# Controller_main.net
KiCad netlist of a schematic drawn in EAGLE
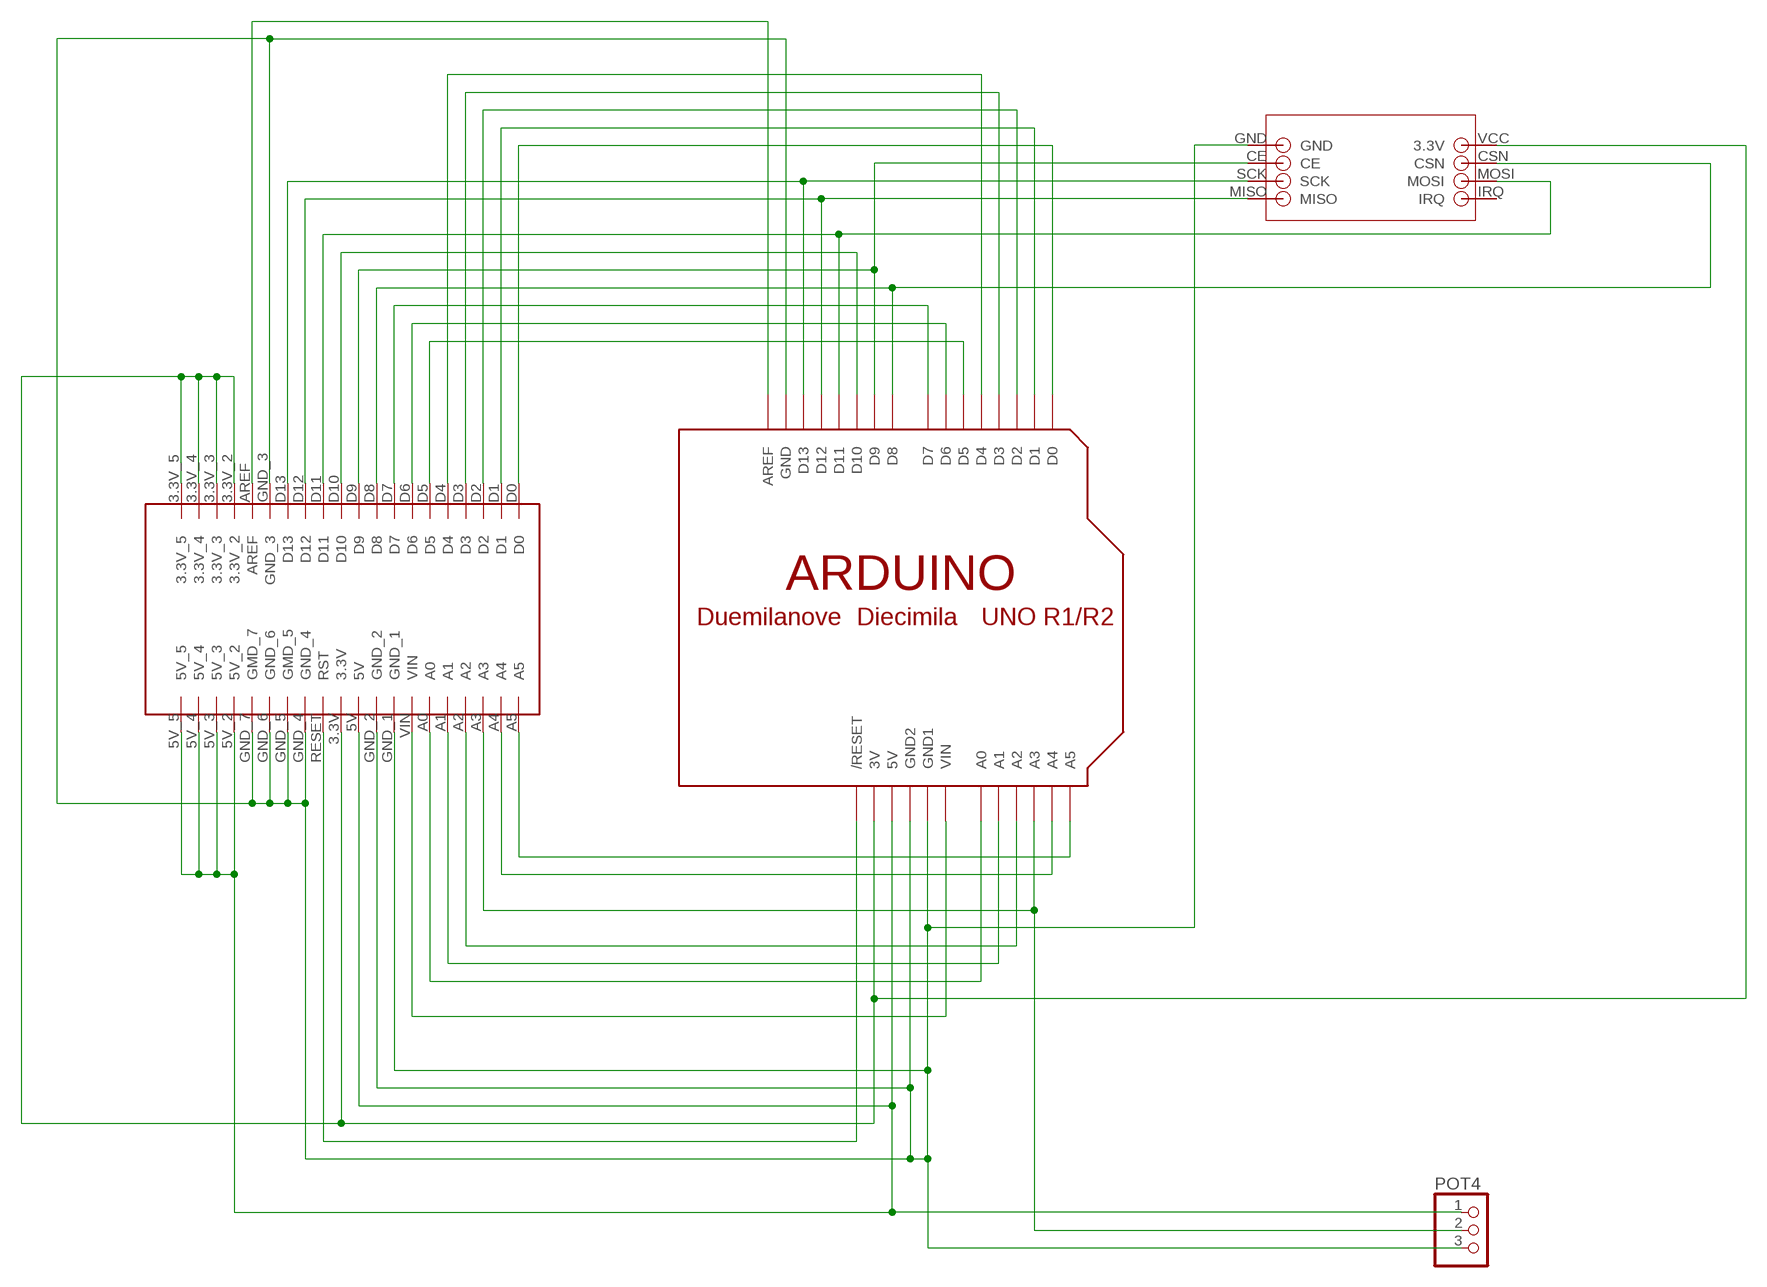
[diagram p0: schematic, sheet 1]

(export (version "E")
  (design (tool "Eeschema 10.0.6"))
  (components
    (comp (ref "2X40CONECTOR1")
      (value "2X40_CONNECTOR")
      (footprint "eagle-import:2X40_PIN_CONNECTOR")
      (libsource (lib "eagle-import") (part "2X40_CONNECTOR"))
    )
    (comp (ref "NRF24L1")
      (value "NRF24L01")
      (footprint "eagle-import:NRF24L01")
      (libsource (lib "eagle-import") (part "NRF24L01"))
    )
    (comp (ref "POT4")
      (value "PINHD-1X3")
      (footprint "eagle-import:1X03")
      (libsource (lib "eagle-import") (part "PINHD-1X3"))
    )
    (comp (ref "U$1")
      (value "ARDUINOUNO")
      (footprint "eagle-import:ARDUINO")
      (libsource (lib "eagle-import") (part "ARDUINOUNO"))
    )
  )
  (nets
    (net (code "1") (name "Net-(2X40CONECTOR1-GMD_5)") (class "Default")
      (node (ref "2X40CONECTOR1") (pin "GND_1") (pinfunction "GND_1_GND_1") (pintype "bidirectional"))
      (node (ref "2X40CONECTOR1") (pin "GND_2") (pinfunction "GND_2_GND_2") (pintype "bidirectional"))
      (node (ref "2X40CONECTOR1") (pin "GND_3") (pinfunction "GND_3_GND_3") (pintype "bidirectional"))
      (node (ref "2X40CONECTOR1") (pin "GND_4") (pinfunction "GND_4_GND_4") (pintype "bidirectional"))
      (node (ref "2X40CONECTOR1") (pin "GND_5") (pinfunction "GMD_5_GND_5") (pintype "bidirectional"))
      (node (ref "2X40CONECTOR1") (pin "GND_6") (pinfunction "GND_6_GND_6") (pintype "bidirectional"))
      (node (ref "2X40CONECTOR1") (pin "GND_7") (pinfunction "GMD_7_GND_7") (pintype "bidirectional"))
      (node (ref "NRF24L1") (pin "GND") (pinfunction "GND_GND") (pintype "bidirectional"))
      (node (ref "POT4") (pin "3") (pinfunction "3_3") (pintype "passive"))
      (node (ref "U$1") (pin "GND") (pinfunction "GND_GND") (pintype "power_in"))
      (node (ref "U$1") (pin "GND1") (pinfunction "GND1_GND1") (pintype "power_in"))
      (node (ref "U$1") (pin "GND2") (pinfunction "GND2_GND2") (pintype "power_in"))
    )
    (net (code "2") (name "Net-(2X40CONECTOR1-Pad5V)") (class "Default")
      (node (ref "2X40CONECTOR1") (pin "5V") (pinfunction "5V_5V") (pintype "bidirectional"))
      (node (ref "2X40CONECTOR1") (pin "5V_2") (pinfunction "5V_2_5V_2") (pintype "bidirectional"))
      (node (ref "2X40CONECTOR1") (pin "5V_3") (pinfunction "5V_3_5V_3") (pintype "bidirectional"))
      (node (ref "2X40CONECTOR1") (pin "5V_4") (pinfunction "5V_4_5V_4") (pintype "bidirectional"))
      (node (ref "2X40CONECTOR1") (pin "5V_5") (pinfunction "5V_5_5V_5") (pintype "bidirectional"))
      (node (ref "POT4") (pin "1") (pinfunction "1_1") (pintype "passive"))
      (node (ref "U$1") (pin "5V") (pinfunction "5V_5V") (pintype "power_in"))
    )
    (net (code "3") (name "Net-(2X40CONECTOR1-PadA0)") (class "Default")
      (node (ref "2X40CONECTOR1") (pin "A0") (pinfunction "A0_A0") (pintype "bidirectional"))
      (node (ref "U$1") (pin "A0") (pinfunction "A0_A0") (pintype "bidirectional"))
    )
    (net (code "4") (name "Net-(2X40CONECTOR1-PadA1)") (class "Default")
      (node (ref "2X40CONECTOR1") (pin "A1") (pinfunction "A1_A1") (pintype "bidirectional"))
      (node (ref "U$1") (pin "A1") (pinfunction "A1_A1") (pintype "bidirectional"))
    )
    (net (code "5") (name "Net-(2X40CONECTOR1-PadA2)") (class "Default")
      (node (ref "2X40CONECTOR1") (pin "A2") (pinfunction "A2_A2") (pintype "bidirectional"))
      (node (ref "U$1") (pin "A2") (pinfunction "A2_A2") (pintype "bidirectional"))
    )
    (net (code "6") (name "Net-(2X40CONECTOR1-PadA3)") (class "Default")
      (node (ref "2X40CONECTOR1") (pin "A3") (pinfunction "A3_A3") (pintype "bidirectional"))
      (node (ref "POT4") (pin "2") (pinfunction "2_2") (pintype "passive"))
      (node (ref "U$1") (pin "A3") (pinfunction "A3_A3") (pintype "bidirectional"))
    )
    (net (code "7") (name "Net-(2X40CONECTOR1-PadA4)") (class "Default")
      (node (ref "2X40CONECTOR1") (pin "A4") (pinfunction "A4_A4") (pintype "bidirectional"))
      (node (ref "U$1") (pin "A4") (pinfunction "A4_A4") (pintype "bidirectional"))
    )
    (net (code "8") (name "Net-(2X40CONECTOR1-PadA5)") (class "Default")
      (node (ref "2X40CONECTOR1") (pin "A5") (pinfunction "A5_A5") (pintype "bidirectional"))
      (node (ref "U$1") (pin "A5") (pinfunction "A5_A5") (pintype "bidirectional"))
    )
    (net (code "9") (name "Net-(2X40CONECTOR1-PadAREF)") (class "Default")
      (node (ref "2X40CONECTOR1") (pin "AREF") (pinfunction "AREF_AREF") (pintype "bidirectional"))
      (node (ref "U$1") (pin "AREF") (pinfunction "AREF_AREF") (pintype "bidirectional"))
    )
    (net (code "10") (name "Net-(2X40CONECTOR1-PadD0)") (class "Default")
      (node (ref "2X40CONECTOR1") (pin "D0") (pinfunction "D0_D0") (pintype "bidirectional"))
      (node (ref "U$1") (pin "D0") (pinfunction "D0_D0") (pintype "bidirectional"))
    )
    (net (code "11") (name "Net-(2X40CONECTOR1-PadD1)") (class "Default")
      (node (ref "2X40CONECTOR1") (pin "D1") (pinfunction "D1_D1") (pintype "bidirectional"))
      (node (ref "U$1") (pin "D1") (pinfunction "D1_D1") (pintype "bidirectional"))
    )
    (net (code "12") (name "Net-(2X40CONECTOR1-PadD2)") (class "Default")
      (node (ref "2X40CONECTOR1") (pin "D2") (pinfunction "D2_D2") (pintype "bidirectional"))
      (node (ref "U$1") (pin "D2") (pinfunction "D2_D2") (pintype "bidirectional"))
    )
    (net (code "13") (name "Net-(2X40CONECTOR1-PadD3)") (class "Default")
      (node (ref "2X40CONECTOR1") (pin "D3") (pinfunction "D3_D3") (pintype "bidirectional"))
      (node (ref "U$1") (pin "D3") (pinfunction "D3_D3") (pintype "bidirectional"))
    )
    (net (code "14") (name "Net-(2X40CONECTOR1-PadD4)") (class "Default")
      (node (ref "2X40CONECTOR1") (pin "D4") (pinfunction "D4_D4") (pintype "bidirectional"))
      (node (ref "U$1") (pin "D4") (pinfunction "D4_D4") (pintype "bidirectional"))
    )
    (net (code "15") (name "Net-(2X40CONECTOR1-PadD5)") (class "Default")
      (node (ref "2X40CONECTOR1") (pin "D5") (pinfunction "D5_D5") (pintype "bidirectional"))
      (node (ref "U$1") (pin "D5") (pinfunction "D5_D5") (pintype "bidirectional"))
    )
    (net (code "16") (name "Net-(2X40CONECTOR1-PadD6)") (class "Default")
      (node (ref "2X40CONECTOR1") (pin "D6") (pinfunction "D6_D6") (pintype "bidirectional"))
      (node (ref "U$1") (pin "D6") (pinfunction "D6_D6") (pintype "bidirectional"))
    )
    (net (code "17") (name "Net-(2X40CONECTOR1-PadD7)") (class "Default")
      (node (ref "2X40CONECTOR1") (pin "D7") (pinfunction "D7_D7") (pintype "bidirectional"))
      (node (ref "U$1") (pin "D7") (pinfunction "D7_D7") (pintype "bidirectional"))
    )
    (net (code "18") (name "Net-(2X40CONECTOR1-PadD8)") (class "Default")
      (node (ref "2X40CONECTOR1") (pin "D8") (pinfunction "D8_D8") (pintype "bidirectional"))
      (node (ref "NRF24L1") (pin "CSN") (pinfunction "CSN_CSN") (pintype "bidirectional"))
      (node (ref "U$1") (pin "D8") (pinfunction "D8_D8") (pintype "bidirectional"))
    )
    (net (code "19") (name "Net-(2X40CONECTOR1-PadD9)") (class "Default")
      (node (ref "2X40CONECTOR1") (pin "D9") (pinfunction "D9_D9") (pintype "bidirectional"))
      (node (ref "NRF24L1") (pin "CE") (pinfunction "CE_CE") (pintype "bidirectional"))
      (node (ref "U$1") (pin "D9") (pinfunction "D9_D9") (pintype "bidirectional"))
    )
    (net (code "20") (name "Net-(2X40CONECTOR1-PadD10)") (class "Default")
      (node (ref "2X40CONECTOR1") (pin "D10") (pinfunction "D10_D10") (pintype "bidirectional"))
      (node (ref "U$1") (pin "D10") (pinfunction "D10_D10") (pintype "bidirectional"))
    )
    (net (code "21") (name "Net-(2X40CONECTOR1-PadD11)") (class "Default")
      (node (ref "2X40CONECTOR1") (pin "D11") (pinfunction "D11_D11") (pintype "bidirectional"))
      (node (ref "NRF24L1") (pin "MOSI") (pinfunction "MOSI_MOSI") (pintype "bidirectional"))
      (node (ref "U$1") (pin "D11") (pinfunction "D11_D11") (pintype "bidirectional"))
    )
    (net (code "22") (name "Net-(2X40CONECTOR1-PadD12)") (class "Default")
      (node (ref "2X40CONECTOR1") (pin "D12") (pinfunction "D12_D12") (pintype "bidirectional"))
      (node (ref "NRF24L1") (pin "MISO") (pinfunction "MISO_MISO") (pintype "bidirectional"))
      (node (ref "U$1") (pin "D12") (pinfunction "D12_D12") (pintype "bidirectional"))
    )
    (net (code "23") (name "Net-(2X40CONECTOR1-PadD13)") (class "Default")
      (node (ref "2X40CONECTOR1") (pin "D13") (pinfunction "D13_D13") (pintype "bidirectional"))
      (node (ref "NRF24L1") (pin "SCK") (pinfunction "SCK_SCK") (pintype "bidirectional"))
      (node (ref "U$1") (pin "D13") (pinfunction "D13_D13") (pintype "bidirectional"))
    )
    (net (code "24") (name "Net-(2X40CONECTOR1-PadVIN)") (class "Default")
      (node (ref "2X40CONECTOR1") (pin "VIN") (pinfunction "VIN_VIN") (pintype "bidirectional"))
      (node (ref "U$1") (pin "VIN") (pinfunction "VIN_VIN") (pintype "power_in"))
    )
    (net (code "25") (name "Net-(2X40CONECTOR1-RST)") (class "Default")
      (node (ref "2X40CONECTOR1") (pin "RESET") (pinfunction "RST_RESET") (pintype "bidirectional"))
      (node (ref "U$1") (pin "RESET") (pinfunction "/RESET_RESET") (pintype "bidirectional"))
    )
    (net (code "26") (name "Net-(NRF24L1-3.3V)") (class "Default")
      (node (ref "2X40CONECTOR1") (pin "3.3V") (pinfunction "3.3V_3.3V") (pintype "bidirectional"))
      (node (ref "2X40CONECTOR1") (pin "3.3V_2") (pinfunction "3.3V_2_3.3V_2") (pintype "bidirectional"))
      (node (ref "2X40CONECTOR1") (pin "3.3V_3") (pinfunction "3.3V_3_3.3V_3") (pintype "bidirectional"))
      (node (ref "2X40CONECTOR1") (pin "3.3V_4") (pinfunction "3.3V_4_3.3V_4") (pintype "bidirectional"))
      (node (ref "2X40CONECTOR1") (pin "3.3V_5") (pinfunction "3.3V_5_3.3V_5") (pintype "bidirectional"))
      (node (ref "NRF24L1") (pin "VCC") (pinfunction "3.3V_VCC") (pintype "bidirectional"))
      (node (ref "U$1") (pin "3V") (pinfunction "3V_3V") (pintype "power_in"))
    )
    (net (code "27") (name "unconnected-(NRF24L1-PadIRQ)") (class "Default")
      (node (ref "NRF24L1") (pin "IRQ") (pinfunction "IRQ_IRQ") (pintype "bidirectional"))
    )
  )
)
